# five_poke_1_0.net
KiCad netlist of a schematic drawn in EAGLE
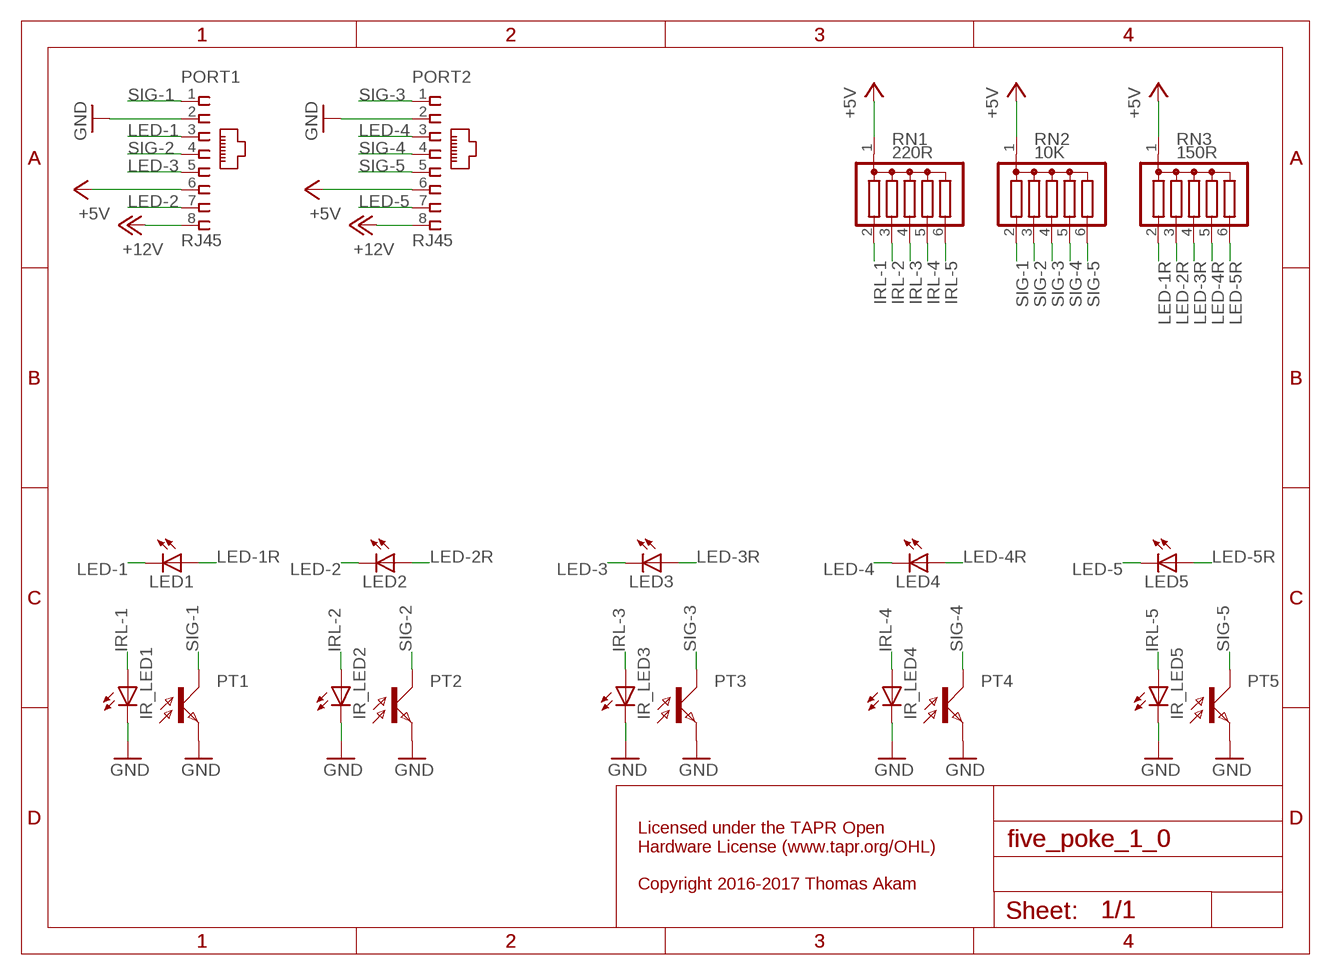
[diagram p0: schematic, sheet 1]

(export (version "E")
  (design (tool "Eeschema 10.0.6"))
  (components
    (comp (ref "IR_LED1")
      (value "LEDIRL80A")
      (footprint "eagle-import:IRL80A")
      (libsource (lib "eagle-import") (part "LEDIRL80A"))
    )
    (comp (ref "IR_LED2")
      (value "LEDIRL80A")
      (footprint "eagle-import:IRL80A")
      (libsource (lib "eagle-import") (part "LEDIRL80A"))
    )
    (comp (ref "IR_LED3")
      (value "LEDIRL80A")
      (footprint "eagle-import:IRL80A")
      (libsource (lib "eagle-import") (part "LEDIRL80A"))
    )
    (comp (ref "IR_LED4")
      (value "LEDIRL80A")
      (footprint "eagle-import:IRL80A")
      (libsource (lib "eagle-import") (part "LEDIRL80A"))
    )
    (comp (ref "IR_LED5")
      (value "LEDIRL80A")
      (footprint "eagle-import:IRL80A")
      (libsource (lib "eagle-import") (part "LEDIRL80A"))
    )
    (comp (ref "LED1")
      (value "LEDSML0805")
      (footprint "eagle-import:SML0805")
      (libsource (lib "eagle-import") (part "LEDSML0805"))
    )
    (comp (ref "LED2")
      (value "LEDSML0805")
      (footprint "eagle-import:SML0805")
      (libsource (lib "eagle-import") (part "LEDSML0805"))
    )
    (comp (ref "LED3")
      (value "LEDSML0805")
      (footprint "eagle-import:SML0805")
      (libsource (lib "eagle-import") (part "LEDSML0805"))
    )
    (comp (ref "LED4")
      (value "LEDSML0805")
      (footprint "eagle-import:SML0805")
      (libsource (lib "eagle-import") (part "LEDSML0805"))
    )
    (comp (ref "LED5")
      (value "LEDSML0805")
      (footprint "eagle-import:SML0805")
      (libsource (lib "eagle-import") (part "LEDSML0805"))
    )
    (comp (ref "PORT1")
      (value "RJ45")
      (footprint "eagle-import:RJ45-NO-SHIELD-VERTICAL")
      (libsource (lib "eagle-import") (part "RJ45VERTICAL"))
    )
    (comp (ref "PORT2")
      (value "RJ45")
      (footprint "eagle-import:RJ45-NO-SHIELD-VERTICAL")
      (libsource (lib "eagle-import") (part "RJ45VERTICAL"))
    )
    (comp (ref "PT1")
      (value "LPT80A")
      (footprint "eagle-import:LPT80A")
      (fields (field (name "OC_FARNELL") "unknown") (field (name "OC_NEWARK") "unknown"))
      (libsource (lib "eagle-import") (part "LPT80A"))
    )
    (comp (ref "PT2")
      (value "LPT80A")
      (footprint "eagle-import:LPT80A")
      (fields (field (name "OC_FARNELL") "unknown") (field (name "OC_NEWARK") "unknown"))
      (libsource (lib "eagle-import") (part "LPT80A"))
    )
    (comp (ref "PT3")
      (value "LPT80A")
      (footprint "eagle-import:LPT80A")
      (fields (field (name "OC_FARNELL") "unknown") (field (name "OC_NEWARK") "unknown"))
      (libsource (lib "eagle-import") (part "LPT80A"))
    )
    (comp (ref "PT4")
      (value "LPT80A")
      (footprint "eagle-import:LPT80A")
      (fields (field (name "OC_FARNELL") "unknown") (field (name "OC_NEWARK") "unknown"))
      (libsource (lib "eagle-import") (part "LPT80A"))
    )
    (comp (ref "PT5")
      (value "LPT80A")
      (footprint "eagle-import:LPT80A")
      (fields (field (name "OC_FARNELL") "unknown") (field (name "OC_NEWARK") "unknown"))
      (libsource (lib "eagle-import") (part "LPT80A"))
    )
    (comp (ref "RN1")
      (value "220R")
      (footprint "eagle-import:SIL6")
      (libsource (lib "eagle-import") (part "G05R"))
    )
    (comp (ref "RN2")
      (value "10K")
      (footprint "eagle-import:SIL6")
      (libsource (lib "eagle-import") (part "G05R"))
    )
    (comp (ref "RN3")
      (value "150R")
      (footprint "eagle-import:SIL6")
      (libsource (lib "eagle-import") (part "G05R"))
    )
  )
  (nets
    (net (code "1") (name "+5V") (class "Default")
      (node (ref "PORT1") (pin "6") (pinfunction "6_6") (pintype "passive"))
      (node (ref "PORT2") (pin "6") (pinfunction "6_6") (pintype "passive"))
      (node (ref "RN1") (pin "1") (pinfunction "1_1") (pintype "passive"))
      (node (ref "RN2") (pin "1") (pinfunction "1_1") (pintype "passive"))
      (node (ref "RN3") (pin "1") (pinfunction "1_1") (pintype "passive"))
    )
    (net (code "2") (name "+12V") (class "Default")
      (node (ref "PORT1") (pin "8") (pinfunction "8_8") (pintype "passive"))
      (node (ref "PORT2") (pin "8") (pinfunction "8_8") (pintype "passive"))
    )
    (net (code "3") (name "/IRL-1") (class "Default")
      (node (ref "IR_LED1") (pin "A") (pinfunction "A_A") (pintype "passive"))
      (node (ref "RN1") (pin "2") (pinfunction "2_2") (pintype "passive"))
    )
    (net (code "4") (name "/IRL-2") (class "Default")
      (node (ref "IR_LED2") (pin "A") (pinfunction "A_A") (pintype "passive"))
      (node (ref "RN1") (pin "3") (pinfunction "3_3") (pintype "passive"))
    )
    (net (code "5") (name "/IRL-3") (class "Default")
      (node (ref "IR_LED3") (pin "A") (pinfunction "A_A") (pintype "passive"))
      (node (ref "RN1") (pin "4") (pinfunction "4_4") (pintype "passive"))
    )
    (net (code "6") (name "/IRL-4") (class "Default")
      (node (ref "IR_LED4") (pin "A") (pinfunction "A_A") (pintype "passive"))
      (node (ref "RN1") (pin "5") (pinfunction "5_5") (pintype "passive"))
    )
    (net (code "7") (name "/IRL-5") (class "Default")
      (node (ref "IR_LED5") (pin "A") (pinfunction "A_A") (pintype "passive"))
      (node (ref "RN1") (pin "6") (pinfunction "6_6") (pintype "passive"))
    )
    (net (code "8") (name "/LED-1") (class "Default")
      (node (ref "LED1") (pin "C") (pinfunction "C_C") (pintype "passive"))
      (node (ref "PORT1") (pin "3") (pinfunction "3_3") (pintype "passive"))
    )
    (net (code "9") (name "/LED-1R") (class "Default")
      (node (ref "LED1") (pin "A") (pinfunction "A_A") (pintype "passive"))
      (node (ref "RN3") (pin "2") (pinfunction "2_2") (pintype "passive"))
    )
    (net (code "10") (name "/LED-2") (class "Default")
      (node (ref "LED2") (pin "C") (pinfunction "C_C") (pintype "passive"))
      (node (ref "PORT1") (pin "7") (pinfunction "7_7") (pintype "passive"))
    )
    (net (code "11") (name "/LED-2R") (class "Default")
      (node (ref "LED2") (pin "A") (pinfunction "A_A") (pintype "passive"))
      (node (ref "RN3") (pin "3") (pinfunction "3_3") (pintype "passive"))
    )
    (net (code "12") (name "/LED-3") (class "Default")
      (node (ref "LED3") (pin "C") (pinfunction "C_C") (pintype "passive"))
      (node (ref "PORT1") (pin "5") (pinfunction "5_5") (pintype "passive"))
    )
    (net (code "13") (name "/LED-3R") (class "Default")
      (node (ref "LED3") (pin "A") (pinfunction "A_A") (pintype "passive"))
      (node (ref "RN3") (pin "4") (pinfunction "4_4") (pintype "passive"))
    )
    (net (code "14") (name "/LED-4") (class "Default")
      (node (ref "LED4") (pin "C") (pinfunction "C_C") (pintype "passive"))
      (node (ref "PORT2") (pin "3") (pinfunction "3_3") (pintype "passive"))
    )
    (net (code "15") (name "/LED-4R") (class "Default")
      (node (ref "LED4") (pin "A") (pinfunction "A_A") (pintype "passive"))
      (node (ref "RN3") (pin "5") (pinfunction "5_5") (pintype "passive"))
    )
    (net (code "16") (name "/LED-5") (class "Default")
      (node (ref "LED5") (pin "C") (pinfunction "C_C") (pintype "passive"))
      (node (ref "PORT2") (pin "7") (pinfunction "7_7") (pintype "passive"))
    )
    (net (code "17") (name "/LED-5R") (class "Default")
      (node (ref "LED5") (pin "A") (pinfunction "A_A") (pintype "passive"))
      (node (ref "RN3") (pin "6") (pinfunction "6_6") (pintype "passive"))
    )
    (net (code "18") (name "/SIG-1") (class "Default")
      (node (ref "PORT1") (pin "1") (pinfunction "1_1") (pintype "passive"))
      (node (ref "PT1") (pin "C") (pinfunction "C_C") (pintype "passive"))
      (node (ref "RN2") (pin "2") (pinfunction "2_2") (pintype "passive"))
    )
    (net (code "19") (name "/SIG-2") (class "Default")
      (node (ref "PORT1") (pin "4") (pinfunction "4_4") (pintype "passive"))
      (node (ref "PT2") (pin "C") (pinfunction "C_C") (pintype "passive"))
      (node (ref "RN2") (pin "3") (pinfunction "3_3") (pintype "passive"))
    )
    (net (code "20") (name "/SIG-3") (class "Default")
      (node (ref "PORT2") (pin "1") (pinfunction "1_1") (pintype "passive"))
      (node (ref "PT3") (pin "C") (pinfunction "C_C") (pintype "passive"))
      (node (ref "RN2") (pin "4") (pinfunction "4_4") (pintype "passive"))
    )
    (net (code "21") (name "/SIG-4") (class "Default")
      (node (ref "PORT2") (pin "4") (pinfunction "4_4") (pintype "passive"))
      (node (ref "PT4") (pin "C") (pinfunction "C_C") (pintype "passive"))
      (node (ref "RN2") (pin "5") (pinfunction "5_5") (pintype "passive"))
    )
    (net (code "22") (name "/SIG-5") (class "Default")
      (node (ref "PORT2") (pin "5") (pinfunction "5_5") (pintype "passive"))
      (node (ref "PT5") (pin "C") (pinfunction "C_C") (pintype "passive"))
      (node (ref "RN2") (pin "6") (pinfunction "6_6") (pintype "passive"))
    )
    (net (code "23") (name "GND") (class "Default")
      (node (ref "IR_LED1") (pin "K") (pinfunction "C_K") (pintype "passive"))
      (node (ref "IR_LED2") (pin "K") (pinfunction "C_K") (pintype "passive"))
      (node (ref "IR_LED3") (pin "K") (pinfunction "C_K") (pintype "passive"))
      (node (ref "IR_LED4") (pin "K") (pinfunction "C_K") (pintype "passive"))
      (node (ref "IR_LED5") (pin "K") (pinfunction "C_K") (pintype "passive"))
      (node (ref "PORT1") (pin "2") (pinfunction "2_2") (pintype "passive"))
      (node (ref "PORT2") (pin "2") (pinfunction "2_2") (pintype "passive"))
      (node (ref "PT1") (pin "E") (pinfunction "E_E") (pintype "passive"))
      (node (ref "PT2") (pin "E") (pinfunction "E_E") (pintype "passive"))
      (node (ref "PT3") (pin "E") (pinfunction "E_E") (pintype "passive"))
      (node (ref "PT4") (pin "E") (pinfunction "E_E") (pintype "passive"))
      (node (ref "PT5") (pin "E") (pinfunction "E_E") (pintype "passive"))
    )
  )
)
